# SAW_Ctrl.net
KiCad netlist of a schematic drawn in Altium Designer
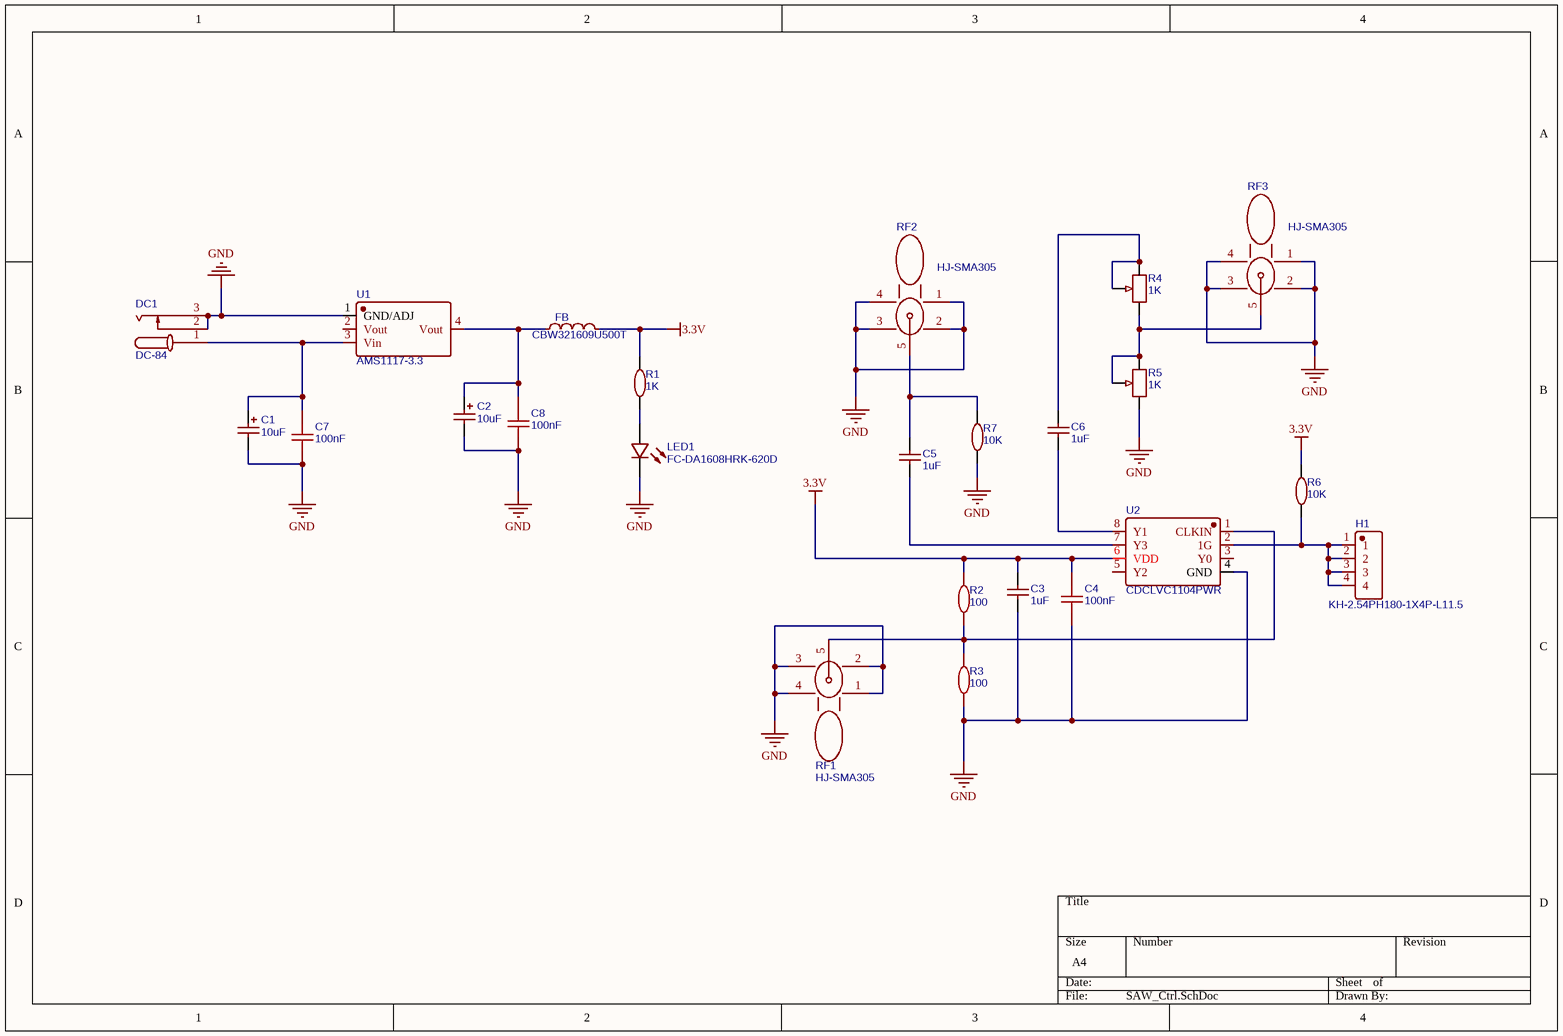
[diagram p0: SAW_Ctrl.SchDoc]

(export (version "E")
  (design (tool "Eeschema 10.0.6"))
  (components
    (comp (ref "C1")
      (value "10uF")
      (footprint "tan10uF:CAP-SMD_L6.0-W3.2-R-RD")
      (description "钽电容10uF")
      (fields
        (field (name "BOM_MANUFACTURER PART") "T491C106K025AT")
        (field (name "BOM_SUPPLIER PART") "C116748")
      )
      (libsource (lib "LPB") (part "10uF_1"))
    )
    (comp (ref "C2")
      (value "10uF")
      (footprint "tan10uF:CAP-SMD_L6.0-W3.2-R-RD")
      (description "钽电容10uF")
      (fields
        (field (name "BOM_MANUFACTURER PART") "T491C106K025AT")
        (field (name "BOM_SUPPLIER PART") "C116748")
      )
      (libsource (lib "LPB") (part "10uF_1"))
    )
    (comp (ref "C3")
      (value "1uF")
      (footprint "Cap1uF:C0603")
      (description "1uF电容")
      (fields
        (field (name "BOM_MANUFACTURER PART") "0603F105M160NT")
        (field (name "BOM_SUPPLIER PART") "C1689")
      )
      (libsource (lib "LPB") (part "1uF"))
    )
    (comp (ref "C4")
      (value "100nF")
      (footprint "Cap100nF:C0603")
      (description "100nF电容")
      (fields
        (field (name "BOM_MANUFACTURER PART") "CL10B104KC8NNNC")
        (field (name "BOM_SUPPLIER PART") "C15725")
      )
      (libsource (lib "LPB") (part "100nF"))
    )
    (comp (ref "C5")
      (value "1uF")
      (footprint "Cap1uF:C0603")
      (description "1uF电容")
      (fields
        (field (name "BOM_MANUFACTURER PART") "0603F105M160NT")
        (field (name "BOM_SUPPLIER PART") "C1689")
      )
      (libsource (lib "LPB") (part "1uF"))
    )
    (comp (ref "C6")
      (value "1uF")
      (footprint "Cap1uF:C0603")
      (description "1uF电容")
      (fields
        (field (name "BOM_MANUFACTURER PART") "0603F105M160NT")
        (field (name "BOM_SUPPLIER PART") "C1689")
      )
      (libsource (lib "LPB") (part "1uF"))
    )
    (comp (ref "C7")
      (value "100nF")
      (footprint "Cap100nF:C0603")
      (description "100nF电容")
      (fields
        (field (name "BOM_MANUFACTURER PART") "CL10B104KC8NNNC")
        (field (name "BOM_SUPPLIER PART") "C15725")
      )
      (libsource (lib "LPB") (part "100nF"))
    )
    (comp (ref "C8")
      (value "100nF")
      (footprint "Cap100nF:C0603")
      (description "100nF电容")
      (fields
        (field (name "BOM_MANUFACTURER PART") "CL10B104KC8NNNC")
        (field (name "BOM_SUPPLIER PART") "C15725")
      )
      (libsource (lib "LPB") (part "100nF"))
    )
    (comp (ref "DC1")
      (value "DC-84")
      (footprint "DCheader:DC-IN-TH_DC-84")
      (description "电源插头")
      (fields (field (name "BOM_SUPPLIER PART") "C718040") (field (name "CONTRIBUTOR") "LCSC"))
      (libsource (lib "LPB") (part "DC-84"))
    )
    (comp (ref "FB")
      (value "CBW321609U500T")
      (footprint "FB50:L1206")
      (description "磁珠50")
      (fields (field (name "BOM_SUPPLIER PART") "C361673") (field (name "CONTRIBUTOR") "LCSC"))
      (libsource (lib "LPB") (part "CBW321609U500T"))
    )
    (comp (ref "H1")
      (value "KH-2.54PH180-1X4P-L11.5")
      (footprint "Pin1x4:HDR-TH_4P-P2.54-V-M")
      (description "排针1*4")
      (fields (field (name "BOM_SUPPLIER PART") "C2905435") (field (name "CONTRIBUTOR") "LCSC"))
      (libsource (lib "LPB") (part "KH-2.54PH180-1X4P-L11.5"))
    )
    (comp (ref "LED1")
      (value "FC-DA1608HRK-620D")
      (footprint "red_led:LED0603-FD")
      (description "led灯")
      (fields (field (name "BOM_SUPPLIER PART") "C84263"))
      (libsource (lib "LPB") (part "FC-DA1608HRK-620D"))
    )
    (comp (ref "R1")
      (value "1K")
      (footprint "Res1K:R0805")
      (description "电阻1K")
      (fields
        (field (name "BOM_MANUFACTURER PART") "0805W8F1001T5E")
        (field (name "BOM_SUPPLIER PART") "C17513")
      )
      (libsource (lib "LPB") (part "1K"))
    )
    (comp (ref "R2")
      (value "100")
      (footprint "Res100:R0805")
      (description "电阻100")
      (fields
        (field (name "BOM_MANUFACTURER PART") "RS-05K101JT")
        (field (name "BOM_SUPPLIER PART") "C115423")
        (field (name "CONTRIBUTOR") "LCSC")
      )
      (libsource (lib "LPB") (part "100"))
    )
    (comp (ref "R3")
      (value "100")
      (footprint "Res100:R0805")
      (description "电阻100")
      (fields
        (field (name "BOM_MANUFACTURER PART") "RS-05K101JT")
        (field (name "BOM_SUPPLIER PART") "C115423")
        (field (name "CONTRIBUTOR") "LCSC")
      )
      (libsource (lib "LPB") (part "100"))
    )
    (comp (ref "R4")
      (value "1K")
      (footprint "Slide1K:RES-ADJ-TH_3P-L6.8-W6.8-P2.50-L_3323P")
      (description "电位器1K")
      (fields
        (field (name "BOM_SUPPLIER PART") "C118970")
        (field (name "BOM_MANUFACTURER PART") "3323P-1-102")
        (field (name "CONTRIBUTOR") "LCSC")
      )
      (libsource (lib "LPB") (part "1K_1"))
    )
    (comp (ref "R5")
      (value "1K")
      (footprint "Slide1K:RES-ADJ-TH_3P-L6.8-W6.8-P2.50-L_3323P")
      (description "电位器1K")
      (fields
        (field (name "BOM_SUPPLIER PART") "C118970")
        (field (name "BOM_MANUFACTURER PART") "3323P-1-102")
        (field (name "CONTRIBUTOR") "LCSC")
      )
      (libsource (lib "LPB") (part "1K_1"))
    )
    (comp (ref "R6")
      (value "10K")
      (footprint "Res10K:R1206")
      (description "电阻10k")
      (fields
        (field (name "BOM_MANUFACTURER PART") "RS-06K1002FT")
        (field (name "BOM_SUPPLIER PART") "C140407")
      )
      (libsource (lib "LPB") (part "10K"))
    )
    (comp (ref "R7")
      (value "10K")
      (footprint "Res10K:R1206")
      (description "电阻10k")
      (fields
        (field (name "BOM_MANUFACTURER PART") "RS-06K1002FT")
        (field (name "BOM_SUPPLIER PART") "C140407")
      )
      (libsource (lib "LPB") (part "10K"))
    )
    (comp (ref "RF1")
      (value "HJ-SMA305")
      (footprint "SMA:SMA-TH_BWSMA-KWE-Z001")
      (description "SMA母口")
      (fields (field (name "BOM_SUPPLIER PART") "C2693810") (field (name "CONTRIBUTOR") "LCSC"))
      (libsource (lib "LPB") (part "HJ-SMA305"))
    )
    (comp (ref "RF2")
      (value "HJ-SMA305")
      (footprint "SMA:SMA-TH_BWSMA-KWE-Z001")
      (description "SMA母口")
      (fields (field (name "BOM_SUPPLIER PART") "C2693810") (field (name "CONTRIBUTOR") "LCSC"))
      (libsource (lib "LPB") (part "HJ-SMA305"))
    )
    (comp (ref "RF3")
      (value "HJ-SMA305")
      (footprint "SMA:SMA-TH_BWSMA-KWE-Z001")
      (description "SMA母口")
      (fields (field (name "BOM_SUPPLIER PART") "C2693810") (field (name "CONTRIBUTOR") "LCSC"))
      (libsource (lib "LPB") (part "HJ-SMA305"))
    )
    (comp (ref "U1")
      (value "AMS1117-3.3")
      (footprint "ams1117:SOT-223-3_L6.5-W3.4-P2.30-LS7.0-BR")
      (description "降压芯片")
      (fields (field (name "BOM_SUPPLIER PART") "C6186"))
      (libsource (lib "LPB") (part "AMS1117-3.3"))
    )
    (comp (ref "U2")
      (value "CDCLVC1104PWR")
      (footprint "CDCLVC1104PWR:TSSOP-8_L4.4-W3.0-P0.65-LS6.4-BL")
      (description "缓冲芯片")
      (fields (field (name "BOM_SUPPLIER PART") "C485518") (field (name "CONTRIBUTOR") "LCSC"))
      (libsource (lib "LPB") (part "CDCLVC1104PWR"))
    )
  )
  (nets
    (net (code "1") (name "3.3V") (class "Default")
      (node (ref "C3") (pin "2") (pinfunction "2_2") (pintype "passive"))
      (node (ref "C4") (pin "2") (pinfunction "2_2") (pintype "passive"))
      (node (ref "FB") (pin "2") (pinfunction "2_2") (pintype "passive"))
      (node (ref "R1") (pin "2") (pinfunction "2_2") (pintype "passive"))
      (node (ref "R2") (pin "2") (pinfunction "2_2") (pintype "passive"))
      (node (ref "R6") (pin "2") (pinfunction "2_2") (pintype "passive"))
      (node (ref "U2") (pin "6") (pinfunction "VDD_6") (pintype "passive"))
    )
    (net (code "2") (name "GND") (class "Default")
      (node (ref "C1") (pin "2") (pinfunction "2_2") (pintype "passive"))
      (node (ref "C2") (pin "2") (pinfunction "2_2") (pintype "passive"))
      (node (ref "C3") (pin "1") (pinfunction "1_1") (pintype "passive"))
      (node (ref "C4") (pin "1") (pinfunction "1_1") (pintype "passive"))
      (node (ref "C7") (pin "1") (pinfunction "1_1") (pintype "passive"))
      (node (ref "C8") (pin "1") (pinfunction "1_1") (pintype "passive"))
      (node (ref "DC1") (pin "2") (pinfunction "2_2") (pintype "passive"))
      (node (ref "DC1") (pin "3") (pinfunction "3_3") (pintype "passive"))
      (node (ref "LED1") (pin "2") (pinfunction "K_2") (pintype "passive"))
      (node (ref "R3") (pin "1") (pinfunction "1_1") (pintype "passive"))
      (node (ref "R5") (pin "1") (pinfunction "1_1") (pintype "passive"))
      (node (ref "R7") (pin "1") (pinfunction "1_1") (pintype "passive"))
      (node (ref "RF1") (pin "1") (pinfunction "1_1") (pintype "passive"))
      (node (ref "RF1") (pin "2") (pinfunction "2_2") (pintype "passive"))
      (node (ref "RF1") (pin "3") (pinfunction "3_3") (pintype "passive"))
      (node (ref "RF1") (pin "4") (pinfunction "4_4") (pintype "passive"))
      (node (ref "RF2") (pin "1") (pinfunction "1_1") (pintype "passive"))
      (node (ref "RF2") (pin "2") (pinfunction "2_2") (pintype "passive"))
      (node (ref "RF2") (pin "3") (pinfunction "3_3") (pintype "passive"))
      (node (ref "RF2") (pin "4") (pinfunction "4_4") (pintype "passive"))
      (node (ref "RF3") (pin "1") (pinfunction "1_1") (pintype "passive"))
      (node (ref "RF3") (pin "2") (pinfunction "2_2") (pintype "passive"))
      (node (ref "RF3") (pin "3") (pinfunction "3_3") (pintype "passive"))
      (node (ref "RF3") (pin "4") (pinfunction "4_4") (pintype "passive"))
      (node (ref "U1") (pin "1") (pinfunction "GND/ADJ_1") (pintype "passive"))
      (node (ref "U2") (pin "4") (pinfunction "GND_4") (pintype "passive"))
    )
    (net (code "3") (name "Net-(C2-Pad1)") (class "Default")
      (node (ref "C2") (pin "1") (pinfunction "1_1") (pintype "passive"))
      (node (ref "C8") (pin "2") (pinfunction "2_2") (pintype "passive"))
      (node (ref "FB") (pin "1") (pinfunction "1_1") (pintype "passive"))
      (node (ref "U1") (pin "4") (pinfunction "Vout_4") (pintype "passive"))
    )
    (net (code "4") (name "Net-(C5-Pad2)") (class "Default")
      (node (ref "C5") (pin "2") (pinfunction "2_2") (pintype "passive"))
      (node (ref "R7") (pin "2") (pinfunction "2_2") (pintype "passive"))
      (node (ref "RF2") (pin "5") (pinfunction "5_5") (pintype "passive"))
    )
    (net (code "5") (name "Net-(C6-Pad2)") (class "Default")
      (node (ref "C6") (pin "2") (pinfunction "2_2") (pintype "passive"))
      (node (ref "R4") (pin "2") (pinfunction "2_2") (pintype "passive"))
      (node (ref "R4") (pin "3") (pinfunction "3_3") (pintype "passive"))
    )
    (net (code "6") (name "Net-(LED1-A)") (class "Default")
      (node (ref "LED1") (pin "1") (pinfunction "A_1") (pintype "passive"))
      (node (ref "R1") (pin "1") (pinfunction "1_1") (pintype "passive"))
    )
    (net (code "7") (name "Net-(R4-Pad1)") (class "Default")
      (node (ref "R4") (pin "1") (pinfunction "1_1") (pintype "passive"))
      (node (ref "R5") (pin "2") (pinfunction "2_2") (pintype "passive"))
      (node (ref "R5") (pin "3") (pinfunction "3_3") (pintype "passive"))
      (node (ref "RF3") (pin "5") (pinfunction "5_5") (pintype "passive"))
    )
    (net (code "8") (name "Net-(U1-Vin)") (class "Default")
      (node (ref "C1") (pin "1") (pinfunction "1_1") (pintype "passive"))
      (node (ref "C7") (pin "2") (pinfunction "2_2") (pintype "passive"))
      (node (ref "DC1") (pin "1") (pinfunction "1_1") (pintype "passive"))
      (node (ref "U1") (pin "3") (pinfunction "Vin_3") (pintype "passive"))
    )
    (net (code "9") (name "Net-(U2-1G)") (class "Default")
      (node (ref "H1") (pin "1") (pinfunction "1_1") (pintype "passive"))
      (node (ref "H1") (pin "2") (pinfunction "2_2") (pintype "passive"))
      (node (ref "H1") (pin "3") (pinfunction "3_3") (pintype "passive"))
      (node (ref "H1") (pin "4") (pinfunction "4_4") (pintype "passive"))
      (node (ref "R6") (pin "1") (pinfunction "1_1") (pintype "passive"))
      (node (ref "U2") (pin "2") (pinfunction "1G_2") (pintype "passive"))
    )
    (net (code "10") (name "Net-(U2-CLKIN)") (class "Default")
      (node (ref "R2") (pin "1") (pinfunction "1_1") (pintype "passive"))
      (node (ref "R3") (pin "2") (pinfunction "2_2") (pintype "passive"))
      (node (ref "RF1") (pin "5") (pinfunction "5_5") (pintype "passive"))
      (node (ref "U2") (pin "1") (pinfunction "CLKIN_1") (pintype "passive"))
    )
    (net (code "11") (name "Net-(U2-Y1)") (class "Default")
      (node (ref "C6") (pin "1") (pinfunction "1_1") (pintype "passive"))
      (node (ref "U2") (pin "8") (pinfunction "Y1_8") (pintype "passive"))
    )
    (net (code "12") (name "Net-(U2-Y3)") (class "Default")
      (node (ref "C5") (pin "1") (pinfunction "1_1") (pintype "passive"))
      (node (ref "U2") (pin "7") (pinfunction "Y3_7") (pintype "passive"))
    )
    (net (code "13") (name "unconnected-(U1-Vout-Pad2)") (class "Default")
      (node (ref "U1") (pin "2") (pinfunction "Vout_2") (pintype "passive"))
    )
    (net (code "14") (name "unconnected-(U2-Y0-Pad3)") (class "Default")
      (node (ref "U2") (pin "3") (pinfunction "Y0_3") (pintype "passive"))
    )
    (net (code "15") (name "unconnected-(U2-Y2-Pad5)") (class "Default")
      (node (ref "U2") (pin "5") (pinfunction "Y2_5") (pintype "passive"))
    )
  )
)
